# serpentine.net
KiCad netlist of a schematic drawn in Altium Designer
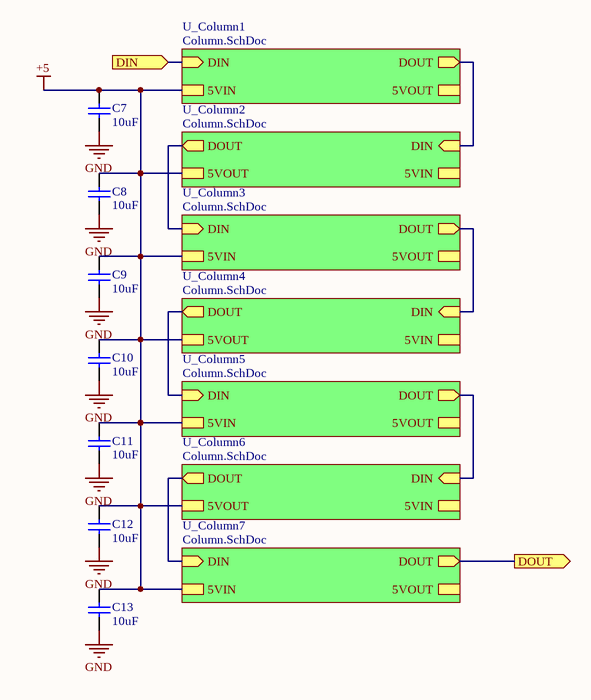
[diagram p0: serpentine.SchDoc]

(export (version "E")
  (design (tool "Eeschema 10.0.6"))
  (components
    (comp (ref "C7")
      (value "10uF")
      (footprint "CAP1206")
      (description "C342827")
      (fields (field (name "TOLERANCE") "10%"))
      (libsource (lib "blandat") (part "CAP"))
    )
    (comp (ref "C8")
      (value "10uF")
      (footprint "CAP1206")
      (description "C342827")
      (fields (field (name "TOLERANCE") "10%"))
      (libsource (lib "blandat") (part "CAP"))
    )
    (comp (ref "C9")
      (value "10uF")
      (footprint "CAP1206")
      (description "C342827")
      (fields (field (name "TOLERANCE") "10%"))
      (libsource (lib "blandat") (part "CAP"))
    )
    (comp (ref "C10")
      (value "10uF")
      (footprint "CAP1206")
      (description "C342827")
      (fields (field (name "TOLERANCE") "10%"))
      (libsource (lib "blandat") (part "CAP"))
    )
    (comp (ref "C11")
      (value "10uF")
      (footprint "CAP1206")
      (description "C342827")
      (fields (field (name "TOLERANCE") "10%"))
      (libsource (lib "blandat") (part "CAP"))
    )
    (comp (ref "C12")
      (value "10uF")
      (footprint "CAP1206")
      (description "C342827")
      (fields (field (name "TOLERANCE") "10%"))
      (libsource (lib "blandat") (part "CAP"))
    )
    (comp (ref "C13")
      (value "10uF")
      (footprint "CAP1206")
      (description "C342827")
      (fields (field (name "TOLERANCE") "10%"))
      (libsource (lib "blandat") (part "CAP"))
    )
  )
  (nets
    (net (code "1") (name "+5") (class "Default")
      (node (ref "C10") (pin "2") (pinfunction "2_2") (pintype "passive"))
      (node (ref "C11") (pin "2") (pinfunction "2_2") (pintype "passive"))
      (node (ref "C12") (pin "2") (pinfunction "2_2") (pintype "passive"))
      (node (ref "C13") (pin "2") (pinfunction "2_2") (pintype "passive"))
      (node (ref "C7") (pin "2") (pinfunction "2_2") (pintype "passive"))
      (node (ref "C8") (pin "2") (pinfunction "2_2") (pintype "passive"))
      (node (ref "C9") (pin "2") (pinfunction "2_2") (pintype "passive"))
    )
    (net (code "17") (name "GND") (class "Default")
      (node (ref "C10") (pin "1") (pinfunction "1_1") (pintype "passive"))
      (node (ref "C11") (pin "1") (pinfunction "1_1") (pintype "passive"))
      (node (ref "C12") (pin "1") (pinfunction "1_1") (pintype "passive"))
      (node (ref "C13") (pin "1") (pinfunction "1_1") (pintype "passive"))
      (node (ref "C7") (pin "1") (pinfunction "1_1") (pintype "passive"))
      (node (ref "C8") (pin "1") (pinfunction "1_1") (pintype "passive"))
      (node (ref "C9") (pin "1") (pinfunction "1_1") (pintype "passive"))
    )
  )
)
